# ghc-silk.net
KiCad netlist of a schematic drawn in EAGLE
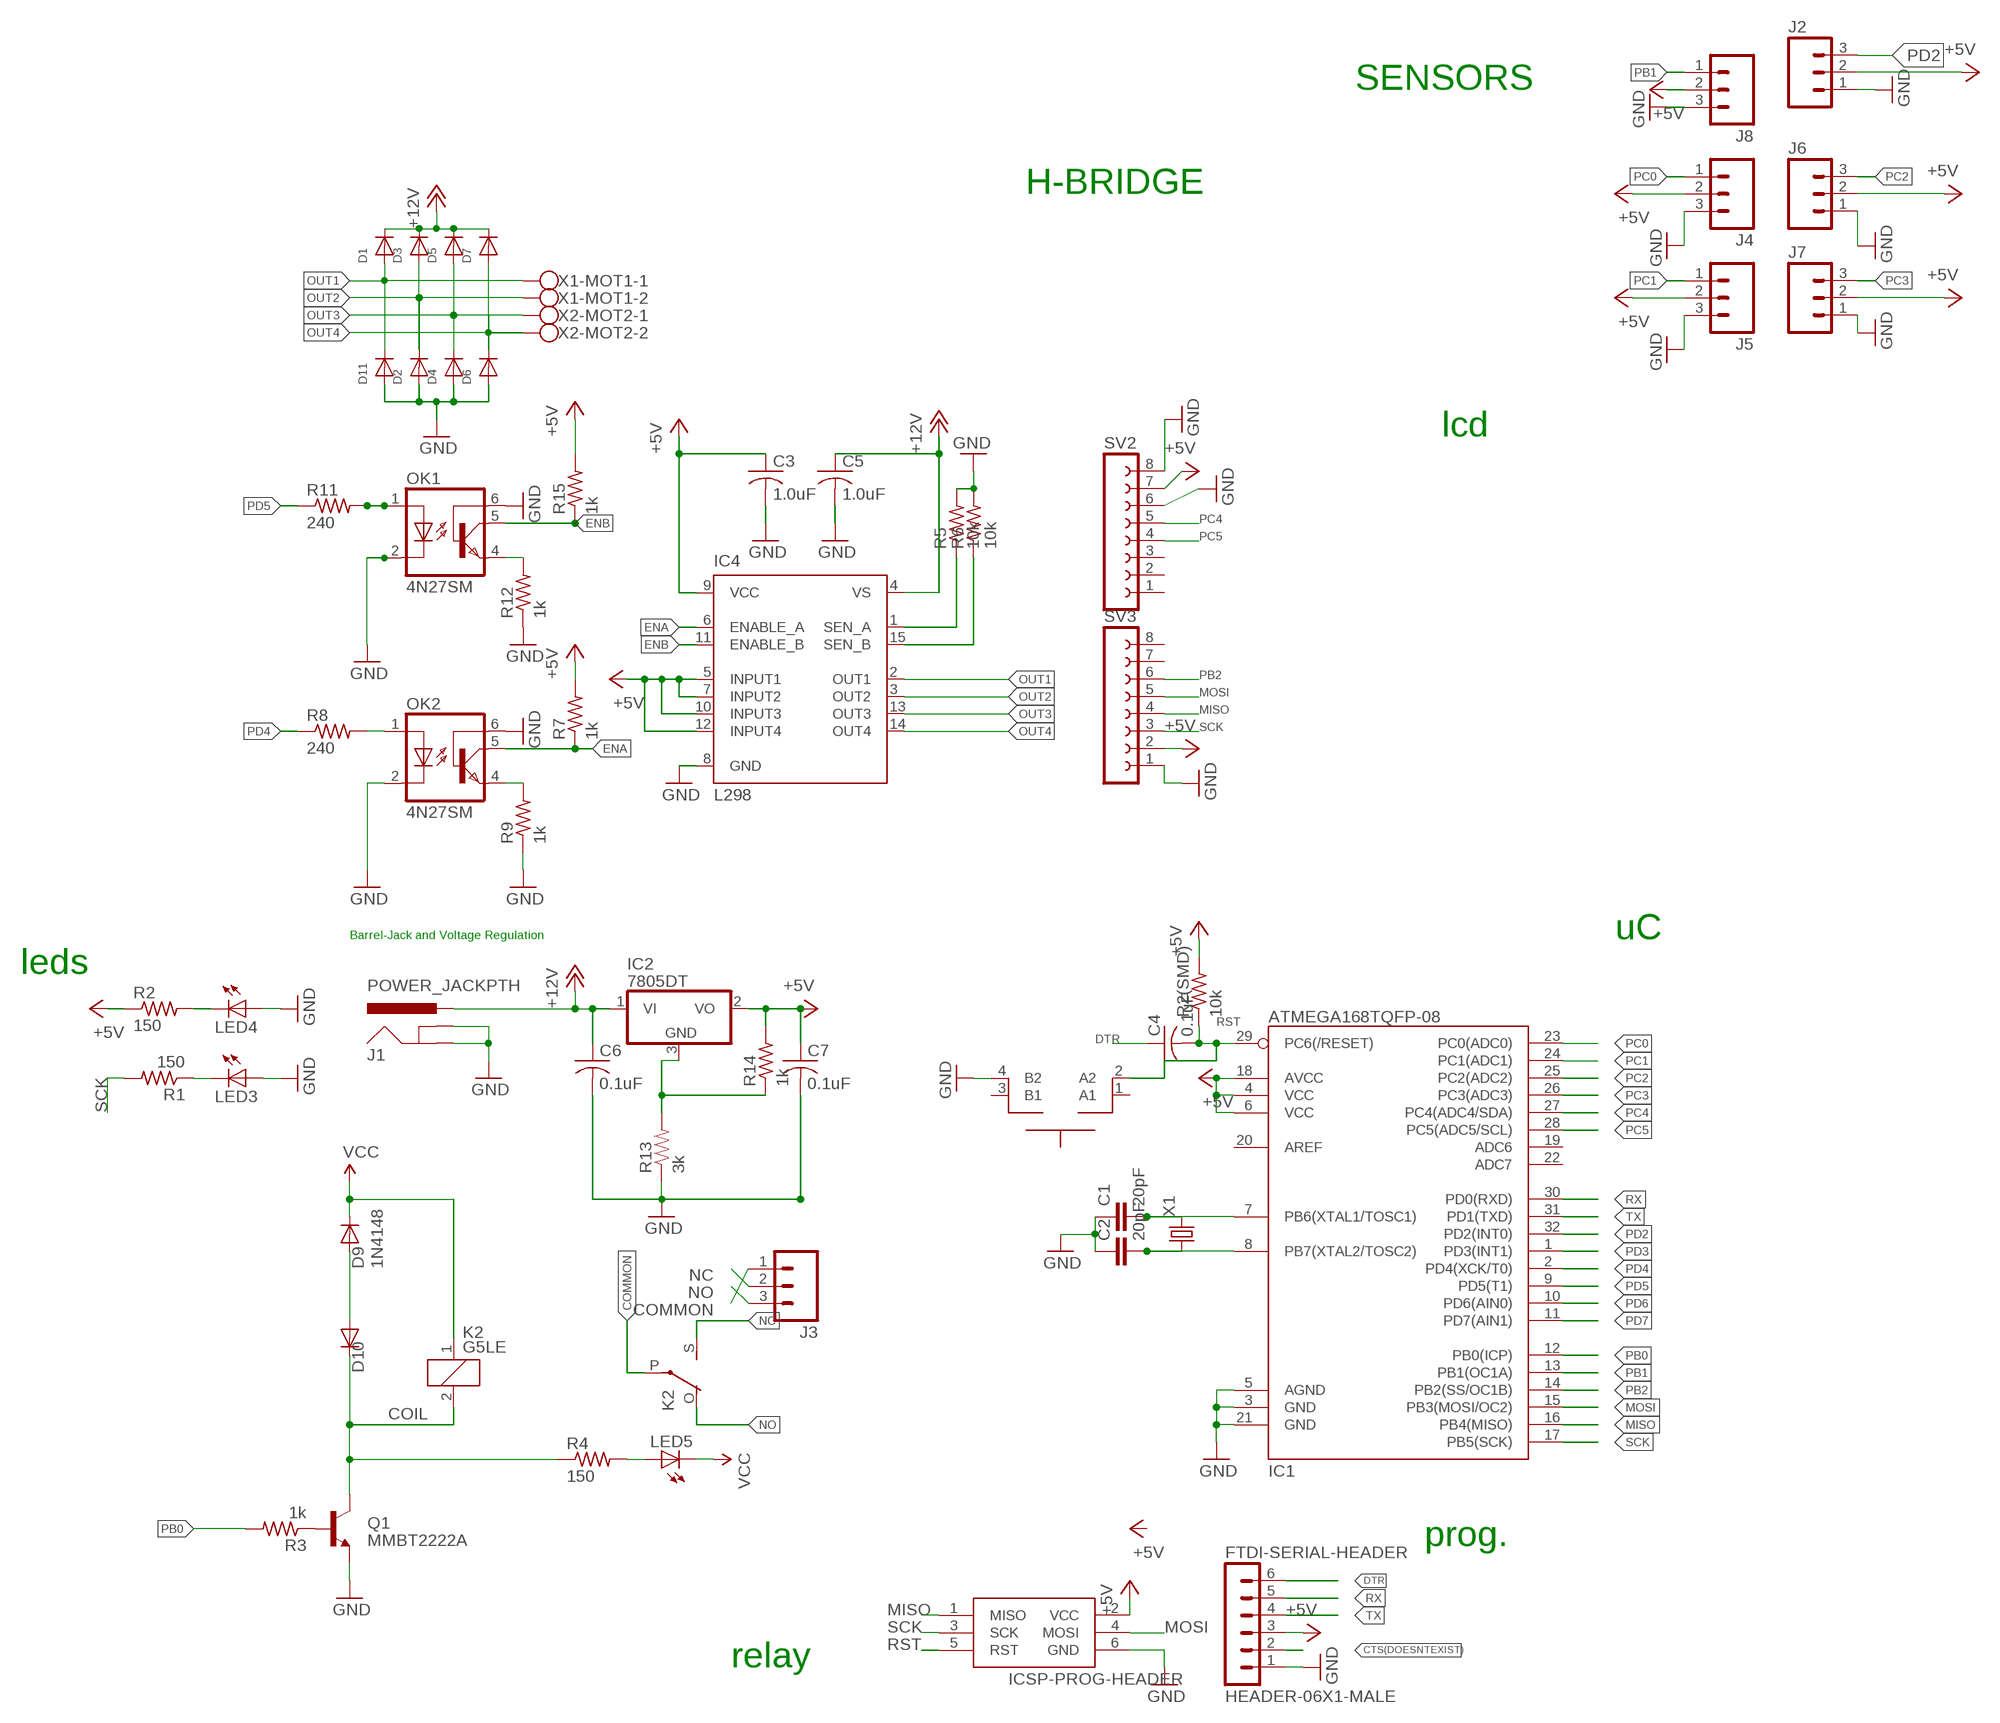
[diagram p0: schematic, sheet 1]

(export (version "E")
  (design (tool "Eeschema 10.0.6"))
  (components
    (comp (ref "C1")
      (value "20pF")
      (footprint "eagle-import:C0805")
      (libsource (lib "eagle-import") (part "C-EUC0805"))
    )
    (comp (ref "C2")
      (value "20pF")
      (footprint "eagle-import:C0805")
      (libsource (lib "eagle-import") (part "C-EUC0805"))
    )
    (comp (ref "C3")
      (value "1.0uF")
      (footprint "eagle-import:C0805")
      (libsource (lib "eagle-import") (part "C-USC0805"))
    )
    (comp (ref "C4")
      (value "0.1uF")
      (footprint "eagle-import:C0805")
      (libsource (lib "eagle-import") (part "C-USC0805"))
    )
    (comp (ref "C5")
      (value "1.0uF")
      (footprint "eagle-import:C0805")
      (libsource (lib "eagle-import") (part "C-USC0805"))
    )
    (comp (ref "C6")
      (value "0.1uF")
      (footprint "eagle-import:C0805")
      (libsource (lib "eagle-import") (part "C-USC0805"))
    )
    (comp (ref "C7")
      (value "0.1uF")
      (footprint "eagle-import:C0805")
      (libsource (lib "eagle-import") (part "C-USC0805"))
    )
    (comp (ref "D1")
      (value "DIODESOD-523")
      (footprint "eagle-import:SOD-523")
      (libsource (lib "eagle-import") (part "DIODESOD-523"))
    )
    (comp (ref "D2")
      (value "DIODESOD-523")
      (footprint "eagle-import:SOD-523")
      (libsource (lib "eagle-import") (part "DIODESOD-523"))
    )
    (comp (ref "D3")
      (value "DIODESOD-523")
      (footprint "eagle-import:SOD-523")
      (libsource (lib "eagle-import") (part "DIODESOD-523"))
    )
    (comp (ref "D4")
      (value "DIODESOD-523")
      (footprint "eagle-import:SOD-523")
      (libsource (lib "eagle-import") (part "DIODESOD-523"))
    )
    (comp (ref "D5")
      (value "DIODESOD-523")
      (footprint "eagle-import:SOD-523")
      (libsource (lib "eagle-import") (part "DIODESOD-523"))
    )
    (comp (ref "D6")
      (value "DIODESOD-523")
      (footprint "eagle-import:SOD-523")
      (libsource (lib "eagle-import") (part "DIODESOD-523"))
    )
    (comp (ref "D7")
      (value "DIODESOD-523")
      (footprint "eagle-import:SOD-523")
      (libsource (lib "eagle-import") (part "DIODESOD-523"))
    )
    (comp (ref "D9")
      (value "1N4148")
      (footprint "eagle-import:SOD-323F")
      (libsource (lib "eagle-import") (part "DIODESOD-323F"))
    )
    (comp (ref "D10")
      (value "Zener")
      (footprint "eagle-import:SOD-323F")
      (libsource (lib "eagle-import") (part "DIODESOD-323F"))
    )
    (comp (ref "D11")
      (value "DIODESOD-523")
      (footprint "eagle-import:SOD-523")
      (libsource (lib "eagle-import") (part "DIODESOD-523"))
    )
    (comp (ref "FTDI-SERIAL-HEADER")
      (value "HEADER-06X1-MALE")
      (footprint "eagle-import:06X1-PTH")
      (libsource (lib "eagle-import") (part "HEADER-06X1?-MALE"))
    )
    (comp (ref "IC1")
      (value "ATMEGA168TQFP-08")
      (footprint "eagle-import:TQFP32-08")
      (libsource (lib "eagle-import") (part "ATMEGA168TQFP-08"))
    )
    (comp (ref "IC2")
      (value "7805DT")
      (footprint "eagle-import:TO252")
      (libsource (lib "eagle-import") (part "78DT05"))
    )
    (comp (ref "IC4")
      (value "L298")
      (footprint "eagle-import:MULTIWATT-15")
      (fields (field (name "MPN") "L298N"))
      (libsource (lib "eagle-import") (part "L298"))
    )
    (comp (ref "ICSP-PROG-HEADER")
      (value "AVRISP-6")
      (footprint "eagle-import:AVRISP")
      (libsource (lib "eagle-import") (part "AVRISP-6"))
    )
    (comp (ref "J1")
      (value "POWER_JACKPTH")
      (footprint "eagle-import:POWER_JACK_PTH")
      (libsource (lib "eagle-import") (part "POWER_JACKPTH"))
    )
    (comp (ref "J2")
      (value "M03SCREW_LOCK")
      (footprint "eagle-import:SCREWTERMINAL-3.5MM-3_LOCK.007S")
      (libsource (lib "eagle-import") (part "M03SCREW_LOCK"))
    )
    (comp (ref "J3")
      (value "M03-SCREW-5MM")
      (footprint "eagle-import:SCREWTERMINAL-5MM-3")
      (libsource (lib "eagle-import") (part "M03-SCREW-5MM"))
    )
    (comp (ref "J4")
      (value "M03SCREW_LOCK")
      (footprint "eagle-import:SCREWTERMINAL-3.5MM-3_LOCK.007S")
      (libsource (lib "eagle-import") (part "M03SCREW_LOCK"))
    )
    (comp (ref "J5")
      (value "M03SCREW_LOCK")
      (footprint "eagle-import:SCREWTERMINAL-3.5MM-3_LOCK.007S")
      (libsource (lib "eagle-import") (part "M03SCREW_LOCK"))
    )
    (comp (ref "J6")
      (value "M03SCREW_LOCK")
      (footprint "eagle-import:SCREWTERMINAL-3.5MM-3_LOCK.007S")
      (libsource (lib "eagle-import") (part "M03SCREW_LOCK"))
    )
    (comp (ref "J7")
      (value "M03SCREW_LOCK")
      (footprint "eagle-import:SCREWTERMINAL-3.5MM-3_LOCK.007S")
      (libsource (lib "eagle-import") (part "M03SCREW_LOCK"))
    )
    (comp (ref "J8")
      (value "M03SCREW_LOCK")
      (footprint "eagle-import:SCREWTERMINAL-3.5MM-3_LOCK.007S")
      (libsource (lib "eagle-import") (part "M03SCREW_LOCK"))
    )
    (comp (ref "K2")
      (value "G5LE")
      (footprint "eagle-import:G5LE")
      (libsource (lib "eagle-import") (part "G5LE"))
    )
    (comp (ref "LED3")
      (value "LEDCHIP-LED0805")
      (footprint "eagle-import:CHIP-LED0805")
      (libsource (lib "eagle-import") (part "LEDCHIP-LED0805"))
    )
    (comp (ref "LED4")
      (value "LEDCHIP-LED0805")
      (footprint "eagle-import:CHIP-LED0805")
      (libsource (lib "eagle-import") (part "LEDCHIP-LED0805"))
    )
    (comp (ref "LED5")
      (value "LEDCHIP-LED0805")
      (footprint "eagle-import:CHIP-LED0805")
      (libsource (lib "eagle-import") (part "LEDCHIP-LED0805"))
    )
    (comp (ref "OK1")
      (value "4N27SM")
      (footprint "eagle-import:DIL6-SMD")
      (fields (field (name "MF") "FAIRCHILD SEMICONDUCTOR") (field (name "MPN") "4N27S-M"))
      (libsource (lib "eagle-import") (part "4N?MS27"))
    )
    (comp (ref "OK2")
      (value "4N27SM")
      (footprint "eagle-import:DIL6-SMD")
      (fields (field (name "MF") "FAIRCHILD SEMICONDUCTOR") (field (name "MPN") "4N27S-M"))
      (libsource (lib "eagle-import") (part "4N?MS27"))
    )
    (comp (ref "Q1")
      (value "MMBT2222A")
      (footprint "eagle-import:SOT23-3")
      (libsource (lib "eagle-import") (part "TRANSISTOR_NPNMMBT2222A"))
    )
    (comp (ref "R1")
      (value "150")
      (footprint "eagle-import:M0805")
      (libsource (lib "eagle-import") (part "R-US_M0805"))
    )
    (comp (ref "R2")
      (value "150")
      (footprint "eagle-import:M0805")
      (libsource (lib "eagle-import") (part "R-US_M0805"))
    )
    (comp (ref "R2(SMD)")
      (value "10k")
      (footprint "eagle-import:M0805")
      (libsource (lib "eagle-import") (part "R-US_M0805"))
    )
    (comp (ref "R3")
      (value "1k")
      (footprint "eagle-import:M0805")
      (libsource (lib "eagle-import") (part "R-US_M0805"))
    )
    (comp (ref "R4")
      (value "150")
      (footprint "eagle-import:M0805")
      (libsource (lib "eagle-import") (part "R-US_M0805"))
    )
    (comp (ref "R5")
      (value "10k")
      (footprint "eagle-import:M0805")
      (libsource (lib "eagle-import") (part "R-US_M0805"))
    )
    (comp (ref "R6")
      (value "10k")
      (footprint "eagle-import:M0805")
      (libsource (lib "eagle-import") (part "R-US_M0805"))
    )
    (comp (ref "R7")
      (value "1k")
      (footprint "eagle-import:M0805")
      (libsource (lib "eagle-import") (part "R-US_M0805"))
    )
    (comp (ref "R8")
      (value "240")
      (footprint "eagle-import:M0805")
      (libsource (lib "eagle-import") (part "R-US_M0805"))
    )
    (comp (ref "R9")
      (value "1k")
      (footprint "eagle-import:M0805")
      (libsource (lib "eagle-import") (part "R-US_M0805"))
    )
    (comp (ref "R11")
      (value "240")
      (footprint "eagle-import:M0805")
      (libsource (lib "eagle-import") (part "R-US_M0805"))
    )
    (comp (ref "R12")
      (value "1k")
      (footprint "eagle-import:M0805")
      (libsource (lib "eagle-import") (part "R-US_M0805"))
    )
    (comp (ref "R13")
      (value "3k")
      (footprint "eagle-import:0402-RES")
      (libsource (lib "eagle-import") (part "RESISTOR0402"))
    )
    (comp (ref "R14")
      (value "1k")
      (footprint "eagle-import:M0805")
      (libsource (lib "eagle-import") (part "R-US_M0805"))
    )
    (comp (ref "R15")
      (value "1k")
      (footprint "eagle-import:M0805")
      (libsource (lib "eagle-import") (part "R-US_M0805"))
    )
    (comp (ref "SV2")
      (value "FE08-1")
      (footprint "eagle-import:FE08")
      (libsource (lib "eagle-import") (part "FE08-1"))
    )
    (comp (ref "SV3")
      (value "FE08-1")
      (footprint "eagle-import:FE08")
      (libsource (lib "eagle-import") (part "FE08-1"))
    )
    (comp (ref "SW2")
      (value "MOMENTARYBUTTON")
      (footprint "eagle-import:SPST_NO_SMD")
      (libsource (lib "eagle-import") (part "MOMENTARYBUTTON"))
    )
    (comp (ref "X1")
      (value "CRYSTALHC49UP")
      (footprint "eagle-import:HC49UP")
      (libsource (lib "eagle-import") (part "CRYSTALHC49UP"))
    )
    (comp (ref "X1-MOT1")
      (value "W237-102")
      (footprint "eagle-import:W237-102")
      (fields (field (name "MPN") "237-102"))
      (libsource (lib "eagle-import") (part "W237-102"))
    )
    (comp (ref "X2-MOT2")
      (value "W237-102")
      (footprint "eagle-import:W237-102")
      (fields (field (name "MPN") "237-102"))
      (libsource (lib "eagle-import") (part "W237-102"))
    )
  )
  (nets
    (net (code "1") (name "+5V") (class "Default")
      (node (ref "C3") (pin "1") (pinfunction "1_1") (pintype "passive"))
      (node (ref "C7") (pin "1") (pinfunction "1_1") (pintype "passive"))
      (node (ref "FTDI-SERIAL-HEADER") (pin "3") (pinfunction "3_3") (pintype "passive"))
      (node (ref "IC1") (pin "18") (pinfunction "AVCC_18") (pintype "bidirectional"))
      (node (ref "IC1") (pin "4") (pinfunction "VCC_4") (pintype "bidirectional"))
      (node (ref "IC1") (pin "6") (pinfunction "VCC_6") (pintype "bidirectional"))
      (node (ref "IC2") (pin "2") (pinfunction "VO_2") (pintype "passive"))
      (node (ref "IC4") (pin "10") (pinfunction "INPUT3_10") (pintype "input"))
      (node (ref "IC4") (pin "12") (pinfunction "INPUT4_12") (pintype "input"))
      (node (ref "IC4") (pin "5") (pinfunction "INPUT1_5") (pintype "input"))
      (node (ref "IC4") (pin "7") (pinfunction "INPUT2_7") (pintype "input"))
      (node (ref "IC4") (pin "9") (pinfunction "VCC_9") (pintype "power_in"))
      (node (ref "ICSP-PROG-HEADER") (pin "2") (pinfunction "VCC_2") (pintype "power_in"))
      (node (ref "J2") (pin "2") (pinfunction "2_2") (pintype "passive"))
      (node (ref "J4") (pin "2") (pinfunction "2_2") (pintype "passive"))
      (node (ref "J5") (pin "2") (pinfunction "2_2") (pintype "passive"))
      (node (ref "J6") (pin "2") (pinfunction "2_2") (pintype "passive"))
      (node (ref "J7") (pin "2") (pinfunction "2_2") (pintype "passive"))
      (node (ref "J8") (pin "2") (pinfunction "2_2") (pintype "passive"))
      (node (ref "R14") (pin "2") (pinfunction "2_2") (pintype "passive"))
      (node (ref "R15") (pin "2") (pinfunction "2_2") (pintype "passive"))
      (node (ref "R2") (pin "1") (pinfunction "1_1") (pintype "passive"))
      (node (ref "R2(SMD)") (pin "2") (pinfunction "2_2") (pintype "passive"))
      (node (ref "R7") (pin "2") (pinfunction "2_2") (pintype "passive"))
      (node (ref "SV2") (pin "7") (pinfunction "7_7") (pintype "passive"))
      (node (ref "SV3") (pin "2") (pinfunction "2_2") (pintype "passive"))
    )
    (net (code "2") (name "+12V") (class "Default")
      (node (ref "C5") (pin "1") (pinfunction "1_1") (pintype "passive"))
      (node (ref "C6") (pin "1") (pinfunction "1_1") (pintype "passive"))
      (node (ref "D1") (pin "K") (pinfunction "C_K") (pintype "passive"))
      (node (ref "D3") (pin "K") (pinfunction "C_K") (pintype "passive"))
      (node (ref "D5") (pin "K") (pinfunction "C_K") (pintype "passive"))
      (node (ref "D7") (pin "K") (pinfunction "C_K") (pintype "passive"))
      (node (ref "IC2") (pin "1") (pinfunction "VI_1") (pintype "input"))
      (node (ref "IC4") (pin "4") (pinfunction "VS_4") (pintype "power_in"))
      (node (ref "J1") (pin "PWR") (pinfunction "PWR_PWR") (pintype "bidirectional"))
    )
    (net (code "3") (name "/COIL") (class "Default")
      (node (ref "D10") (pin "C") (pinfunction "C_C") (pintype "passive"))
      (node (ref "K2") (pin "2") (pinfunction "2_2") (pintype "passive"))
      (node (ref "Q1") (pin "3") (pinfunction "C_3") (pintype "passive"))
      (node (ref "R4") (pin "1") (pinfunction "1_1") (pintype "passive"))
    )
    (net (code "4") (name "/RST") (class "Default")
      (node (ref "C4") (pin "2") (pinfunction "2_2") (pintype "passive"))
      (node (ref "IC1") (pin "29") (pinfunction "PC6(/RESET)_29") (pintype "bidirectional"))
      (node (ref "ICSP-PROG-HEADER") (pin "5") (pinfunction "RST_5") (pintype "output"))
      (node (ref "R2(SMD)") (pin "1") (pinfunction "1_1") (pintype "passive"))
      (node (ref "SW2") (pin "2") (pinfunction "A2_2") (pintype "bidirectional"))
    )
    (net (code "5") (name "COMMON") (class "Default")
      (node (ref "J3") (pin "1") (pinfunction "1_1") (pintype "passive"))
      (node (ref "K2") (pin "P") (pinfunction "P_P") (pintype "passive"))
    )
    (net (code "6") (name "CTS(DOESNTEXIST)") (class "Default")
      (node (ref "FTDI-SERIAL-HEADER") (pin "2") (pinfunction "2_2") (pintype "passive"))
    )
    (net (code "7") (name "DTR") (class "Default")
      (node (ref "C4") (pin "1") (pinfunction "1_1") (pintype "passive"))
      (node (ref "FTDI-SERIAL-HEADER") (pin "6") (pinfunction "6_6") (pintype "passive"))
    )
    (net (code "8") (name "ENA") (class "Default")
      (node (ref "IC4") (pin "6") (pinfunction "ENABLE_A_6") (pintype "input"))
      (node (ref "OK2") (pin "5") (pinfunction "COL_5") (pintype "passive"))
      (node (ref "R7") (pin "1") (pinfunction "1_1") (pintype "passive"))
    )
    (net (code "9") (name "ENB") (class "Default")
      (node (ref "IC4") (pin "11") (pinfunction "ENABLE_B_11") (pintype "input"))
      (node (ref "OK1") (pin "5") (pinfunction "COL_5") (pintype "passive"))
      (node (ref "R15") (pin "1") (pinfunction "1_1") (pintype "passive"))
    )
    (net (code "10") (name "GND") (class "Default")
      (node (ref "C1") (pin "1") (pinfunction "1_1") (pintype "passive"))
      (node (ref "C2") (pin "1") (pinfunction "1_1") (pintype "passive"))
      (node (ref "C3") (pin "2") (pinfunction "2_2") (pintype "passive"))
      (node (ref "C5") (pin "2") (pinfunction "2_2") (pintype "passive"))
      (node (ref "C6") (pin "2") (pinfunction "2_2") (pintype "passive"))
      (node (ref "C7") (pin "2") (pinfunction "2_2") (pintype "passive"))
      (node (ref "D11") (pin "A") (pinfunction "A_A") (pintype "passive"))
      (node (ref "D2") (pin "A") (pinfunction "A_A") (pintype "passive"))
      (node (ref "D4") (pin "A") (pinfunction "A_A") (pintype "passive"))
      (node (ref "D6") (pin "A") (pinfunction "A_A") (pintype "passive"))
      (node (ref "FTDI-SERIAL-HEADER") (pin "1") (pinfunction "1_1") (pintype "passive"))
      (node (ref "IC1") (pin "21") (pinfunction "GND_21") (pintype "bidirectional"))
      (node (ref "IC1") (pin "3") (pinfunction "GND_3") (pintype "bidirectional"))
      (node (ref "IC1") (pin "5") (pinfunction "AGND_5") (pintype "bidirectional"))
      (node (ref "IC4") (pin "8") (pinfunction "GND_8") (pintype "power_in"))
      (node (ref "ICSP-PROG-HEADER") (pin "6") (pinfunction "GND_6") (pintype "power_in"))
      (node (ref "J1") (pin "GND") (pinfunction "GND_GND") (pintype "bidirectional"))
      (node (ref "J1") (pin "GNDBREAK") (pinfunction "GNDBREAK_GNDBREAK") (pintype "bidirectional"))
      (node (ref "J2") (pin "1") (pinfunction "1_1") (pintype "passive"))
      (node (ref "J4") (pin "3") (pinfunction "3_3") (pintype "passive"))
      (node (ref "J5") (pin "3") (pinfunction "3_3") (pintype "passive"))
      (node (ref "J6") (pin "1") (pinfunction "1_1") (pintype "passive"))
      (node (ref "J7") (pin "1") (pinfunction "1_1") (pintype "passive"))
      (node (ref "J8") (pin "3") (pinfunction "3_3") (pintype "passive"))
      (node (ref "LED3") (pin "A") (pinfunction "A_A") (pintype "passive"))
      (node (ref "LED4") (pin "A") (pinfunction "A_A") (pintype "passive"))
      (node (ref "OK1") (pin "2") (pinfunction "C_2") (pintype "passive"))
      (node (ref "OK1") (pin "6") (pinfunction "BAS_6") (pintype "passive"))
      (node (ref "OK2") (pin "2") (pinfunction "C_2") (pintype "passive"))
      (node (ref "OK2") (pin "6") (pinfunction "BAS_6") (pintype "passive"))
      (node (ref "Q1") (pin "2") (pinfunction "E_2") (pintype "passive"))
      (node (ref "R12") (pin "1") (pinfunction "1_1") (pintype "passive"))
      (node (ref "R13") (pin "1") (pinfunction "1_1") (pintype "passive"))
      (node (ref "R5") (pin "2") (pinfunction "2_2") (pintype "passive"))
      (node (ref "R6") (pin "2") (pinfunction "2_2") (pintype "passive"))
      (node (ref "R9") (pin "1") (pinfunction "1_1") (pintype "passive"))
      (node (ref "SV2") (pin "6") (pinfunction "6_6") (pintype "passive"))
      (node (ref "SV2") (pin "8") (pinfunction "8_8") (pintype "passive"))
      (node (ref "SV3") (pin "1") (pinfunction "1_1") (pintype "passive"))
      (node (ref "SW2") (pin "4") (pinfunction "B2_4") (pintype "bidirectional"))
    )
    (net (code "11") (name "MISO") (class "Default")
      (node (ref "IC1") (pin "16") (pinfunction "PB4(MISO)_16") (pintype "bidirectional"))
      (node (ref "ICSP-PROG-HEADER") (pin "1") (pinfunction "MISO_1") (pintype "input"))
      (node (ref "SV3") (pin "4") (pinfunction "4_4") (pintype "passive"))
    )
    (net (code "12") (name "MOSI") (class "Default")
      (node (ref "IC1") (pin "15") (pinfunction "PB3(MOSI/OC2)_15") (pintype "bidirectional"))
      (node (ref "ICSP-PROG-HEADER") (pin "4") (pinfunction "MOSI_4") (pintype "output"))
      (node (ref "SV3") (pin "5") (pinfunction "5_5") (pintype "passive"))
    )
    (net (code "13") (name "NC") (class "Default")
      (node (ref "J3") (pin "2") (pinfunction "2_2") (pintype "passive"))
      (node (ref "K2") (pin "S") (pinfunction "S_S") (pintype "passive"))
    )
    (net (code "14") (name "NO") (class "Default")
      (node (ref "J3") (pin "3") (pinfunction "3_3") (pintype "passive"))
      (node (ref "K2") (pin "O") (pinfunction "O_O") (pintype "passive"))
    )
    (net (code "15") (name "Net-(D10-PadA)") (class "Default")
      (node (ref "D10") (pin "A") (pinfunction "A_A") (pintype "passive"))
      (node (ref "D9") (pin "A") (pinfunction "A_A") (pintype "passive"))
    )
    (net (code "16") (name "Net-(IC1-PB6(XTAL1{slash}TOSC1))") (class "Default")
      (node (ref "C1") (pin "2") (pinfunction "2_2") (pintype "passive"))
      (node (ref "IC1") (pin "7") (pinfunction "PB6(XTAL1/TOSC1)_7") (pintype "bidirectional"))
      (node (ref "X1") (pin "2") (pinfunction "2_2") (pintype "passive"))
    )
    (net (code "17") (name "Net-(IC1-PB7(XTAL2{slash}TOSC2))") (class "Default")
      (node (ref "C2") (pin "2") (pinfunction "2_2") (pintype "passive"))
      (node (ref "IC1") (pin "8") (pinfunction "PB7(XTAL2/TOSC2)_8") (pintype "bidirectional"))
      (node (ref "X1") (pin "1") (pinfunction "1_1") (pintype "passive"))
    )
    (net (code "18") (name "Net-(IC2-GND)") (class "Default")
      (node (ref "IC2") (pin "3") (pinfunction "GND_3") (pintype "passive"))
      (node (ref "R13") (pin "2") (pinfunction "2_2") (pintype "passive"))
      (node (ref "R14") (pin "1") (pinfunction "1_1") (pintype "passive"))
    )
    (net (code "19") (name "Net-(IC4-SEN_A)") (class "Default")
      (node (ref "IC4") (pin "1") (pinfunction "SEN_A_1") (pintype "input"))
      (node (ref "R5") (pin "1") (pinfunction "1_1") (pintype "passive"))
    )
    (net (code "20") (name "Net-(IC4-SEN_B)") (class "Default")
      (node (ref "IC4") (pin "15") (pinfunction "SEN_B_15") (pintype "input"))
      (node (ref "R6") (pin "1") (pinfunction "1_1") (pintype "passive"))
    )
    (net (code "21") (name "Net-(LED3-PadC)") (class "Default")
      (node (ref "LED3") (pin "C") (pinfunction "C_C") (pintype "passive"))
      (node (ref "R1") (pin "1") (pinfunction "1_1") (pintype "passive"))
    )
    (net (code "22") (name "Net-(LED4-PadC)") (class "Default")
      (node (ref "LED4") (pin "C") (pinfunction "C_C") (pintype "passive"))
      (node (ref "R2") (pin "2") (pinfunction "2_2") (pintype "passive"))
    )
    (net (code "23") (name "Net-(LED5-PadA)") (class "Default")
      (node (ref "LED5") (pin "A") (pinfunction "A_A") (pintype "passive"))
      (node (ref "R4") (pin "2") (pinfunction "2_2") (pintype "passive"))
    )
    (net (code "24") (name "Net-(OK1-A)") (class "Default")
      (node (ref "OK1") (pin "1") (pinfunction "A_1") (pintype "passive"))
      (node (ref "R11") (pin "2") (pinfunction "2_2") (pintype "passive"))
    )
    (net (code "25") (name "Net-(OK1-EMI)") (class "Default")
      (node (ref "OK1") (pin "4") (pinfunction "EMI_4") (pintype "passive"))
      (node (ref "R12") (pin "2") (pinfunction "2_2") (pintype "passive"))
    )
    (net (code "26") (name "Net-(OK2-A)") (class "Default")
      (node (ref "OK2") (pin "1") (pinfunction "A_1") (pintype "passive"))
      (node (ref "R8") (pin "2") (pinfunction "2_2") (pintype "passive"))
    )
    (net (code "27") (name "Net-(OK2-EMI)") (class "Default")
      (node (ref "OK2") (pin "4") (pinfunction "EMI_4") (pintype "passive"))
      (node (ref "R9") (pin "2") (pinfunction "2_2") (pintype "passive"))
    )
    (net (code "28") (name "Net-(Q1-B)") (class "Default")
      (node (ref "Q1") (pin "1") (pinfunction "B_1") (pintype "passive"))
      (node (ref "R3") (pin "1") (pinfunction "1_1") (pintype "passive"))
    )
    (net (code "29") (name "OUT1") (class "Default")
      (node (ref "D1") (pin "A") (pinfunction "A_A") (pintype "passive"))
      (node (ref "D11") (pin "K") (pinfunction "C_K") (pintype "passive"))
      (node (ref "IC4") (pin "2") (pinfunction "OUT1_2") (pintype "output"))
      (node (ref "X1-MOT1") (pin "1") (pinfunction "KL_1") (pintype "passive"))
    )
    (net (code "30") (name "OUT2") (class "Default")
      (node (ref "D2") (pin "K") (pinfunction "C_K") (pintype "passive"))
      (node (ref "D3") (pin "A") (pinfunction "A_A") (pintype "passive"))
      (node (ref "IC4") (pin "3") (pinfunction "OUT2_3") (pintype "output"))
      (node (ref "X1-MOT1") (pin "2") (pinfunction "KL_2") (pintype "passive"))
    )
    (net (code "31") (name "OUT3") (class "Default")
      (node (ref "D4") (pin "K") (pinfunction "C_K") (pintype "passive"))
      (node (ref "D5") (pin "A") (pinfunction "A_A") (pintype "passive"))
      (node (ref "IC4") (pin "13") (pinfunction "OUT3_13") (pintype "output"))
      (node (ref "X2-MOT2") (pin "1") (pinfunction "KL_1") (pintype "passive"))
    )
    (net (code "32") (name "OUT4") (class "Default")
      (node (ref "D6") (pin "K") (pinfunction "C_K") (pintype "passive"))
      (node (ref "D7") (pin "A") (pinfunction "A_A") (pintype "passive"))
      (node (ref "IC4") (pin "14") (pinfunction "OUT4_14") (pintype "output"))
      (node (ref "X2-MOT2") (pin "2") (pinfunction "KL_2") (pintype "passive"))
    )
    (net (code "33") (name "PB0") (class "Default")
      (node (ref "IC1") (pin "12") (pinfunction "PB0(ICP)_12") (pintype "bidirectional"))
      (node (ref "R3") (pin "2") (pinfunction "2_2") (pintype "passive"))
    )
    (net (code "34") (name "PB1") (class "Default")
      (node (ref "IC1") (pin "13") (pinfunction "PB1(OC1A)_13") (pintype "bidirectional"))
      (node (ref "J8") (pin "1") (pinfunction "1_1") (pintype "passive"))
    )
    (net (code "35") (name "PB2") (class "Default")
      (node (ref "IC1") (pin "14") (pinfunction "PB2(SS/OC1B)_14") (pintype "bidirectional"))
      (node (ref "SV3") (pin "6") (pinfunction "6_6") (pintype "passive"))
    )
    (net (code "36") (name "PC0") (class "Default")
      (node (ref "IC1") (pin "23") (pinfunction "PC0(ADC0)_23") (pintype "bidirectional"))
      (node (ref "J4") (pin "1") (pinfunction "1_1") (pintype "passive"))
    )
    (net (code "37") (name "PC1") (class "Default")
      (node (ref "IC1") (pin "24") (pinfunction "PC1(ADC1)_24") (pintype "bidirectional"))
      (node (ref "J5") (pin "1") (pinfunction "1_1") (pintype "passive"))
    )
    (net (code "38") (name "PC2") (class "Default")
      (node (ref "IC1") (pin "25") (pinfunction "PC2(ADC2)_25") (pintype "bidirectional"))
      (node (ref "J6") (pin "3") (pinfunction "3_3") (pintype "passive"))
    )
    (net (code "39") (name "PC3") (class "Default")
      (node (ref "IC1") (pin "26") (pinfunction "PC3(ADC3)_26") (pintype "bidirectional"))
      (node (ref "J7") (pin "3") (pinfunction "3_3") (pintype "passive"))
    )
    (net (code "40") (name "PC4") (class "Default")
      (node (ref "IC1") (pin "27") (pinfunction "PC4(ADC4/SDA)_27") (pintype "bidirectional"))
      (node (ref "SV2") (pin "5") (pinfunction "5_5") (pintype "passive"))
    )
    (net (code "41") (name "PC5") (class "Default")
      (node (ref "IC1") (pin "28") (pinfunction "PC5(ADC5/SCL)_28") (pintype "bidirectional"))
      (node (ref "SV2") (pin "4") (pinfunction "4_4") (pintype "passive"))
    )
    (net (code "42") (name "PD2") (class "Default")
      (node (ref "IC1") (pin "32") (pinfunction "PD2(INT0)_32") (pintype "bidirectional"))
      (node (ref "J2") (pin "3") (pinfunction "3_3") (pintype "passive"))
    )
    (net (code "43") (name "PD3") (class "Default")
      (node (ref "IC1") (pin "1") (pinfunction "PD3(INT1)_1") (pintype "bidirectional"))
    )
    (net (code "44") (name "PD4") (class "Default")
      (node (ref "IC1") (pin "2") (pinfunction "PD4(XCK/T0)_2") (pintype "bidirectional"))
      (node (ref "R8") (pin "1") (pinfunction "1_1") (pintype "passive"))
    )
    (net (code "45") (name "PD5") (class "Default")
      (node (ref "IC1") (pin "9") (pinfunction "PD5(T1)_9") (pintype "bidirectional"))
      (node (ref "R11") (pin "1") (pinfunction "1_1") (pintype "passive"))
    )
    (net (code "46") (name "PD6") (class "Default")
      (node (ref "IC1") (pin "10") (pinfunction "PD6(AIN0)_10") (pintype "bidirectional"))
    )
    (net (code "47") (name "PD7") (class "Default")
      (node (ref "IC1") (pin "11") (pinfunction "PD7(AIN1)_11") (pintype "bidirectional"))
    )
    (net (code "48") (name "RX") (class "Default")
      (node (ref "FTDI-SERIAL-HEADER") (pin "5") (pinfunction "5_5") (pintype "passive"))
      (node (ref "IC1") (pin "30") (pinfunction "PD0(RXD)_30") (pintype "bidirectional"))
    )
    (net (code "49") (name "SCK") (class "Default")
      (node (ref "IC1") (pin "17") (pinfunction "PB5(SCK)_17") (pintype "bidirectional"))
      (node (ref "ICSP-PROG-HEADER") (pin "3") (pinfunction "SCK_3") (pintype "output"))
      (node (ref "R1") (pin "2") (pinfunction "2_2") (pintype "passive"))
      (node (ref "SV3") (pin "3") (pinfunction "3_3") (pintype "passive"))
    )
    (net (code "50") (name "TX") (class "Default")
      (node (ref "FTDI-SERIAL-HEADER") (pin "4") (pinfunction "4_4") (pintype "passive"))
      (node (ref "IC1") (pin "31") (pinfunction "PD1(TXD)_31") (pintype "bidirectional"))
    )
    (net (code "51") (name "VCC") (class "Default")
      (node (ref "D9") (pin "C") (pinfunction "C_C") (pintype "passive"))
      (node (ref "K2") (pin "1") (pinfunction "1_1") (pintype "passive"))
      (node (ref "LED5") (pin "C") (pinfunction "C_C") (pintype "passive"))
    )
    (net (code "52") (name "unconnected-(IC1-ADC6-Pad19)") (class "Default")
      (node (ref "IC1") (pin "19") (pinfunction "ADC6_19") (pintype "bidirectional"))
    )
    (net (code "53") (name "unconnected-(IC1-ADC7-Pad22)") (class "Default")
      (node (ref "IC1") (pin "22") (pinfunction "ADC7_22") (pintype "bidirectional"))
    )
    (net (code "54") (name "unconnected-(IC1-AREF-Pad20)") (class "Default")
      (node (ref "IC1") (pin "20") (pinfunction "AREF_20") (pintype "bidirectional"))
    )
    (net (code "55") (name "unconnected-(SV2-Pad1)") (class "Default")
      (node (ref "SV2") (pin "1") (pinfunction "1_1") (pintype "passive"))
    )
    (net (code "56") (name "unconnected-(SV2-Pad2)") (class "Default")
      (node (ref "SV2") (pin "2") (pinfunction "2_2") (pintype "passive"))
    )
    (net (code "57") (name "unconnected-(SV2-Pad3)") (class "Default")
      (node (ref "SV2") (pin "3") (pinfunction "3_3") (pintype "passive"))
    )
    (net (code "58") (name "unconnected-(SV3-Pad7)") (class "Default")
      (node (ref "SV3") (pin "7") (pinfunction "7_7") (pintype "passive"))
    )
    (net (code "59") (name "unconnected-(SV3-Pad8)") (class "Default")
      (node (ref "SV3") (pin "8") (pinfunction "8_8") (pintype "passive"))
    )
    (net (code "60") (name "unconnected-(SW2-A1-Pad1)") (class "Default")
      (node (ref "SW2") (pin "1") (pinfunction "A1_1") (pintype "bidirectional"))
    )
    (net (code "61") (name "unconnected-(SW2-B1-Pad3)") (class "Default")
      (node (ref "SW2") (pin "3") (pinfunction "B1_3") (pintype "bidirectional"))
    )
  )
)
